# Linear_regulators.net
KiCad netlist of a schematic drawn in Altium Designer
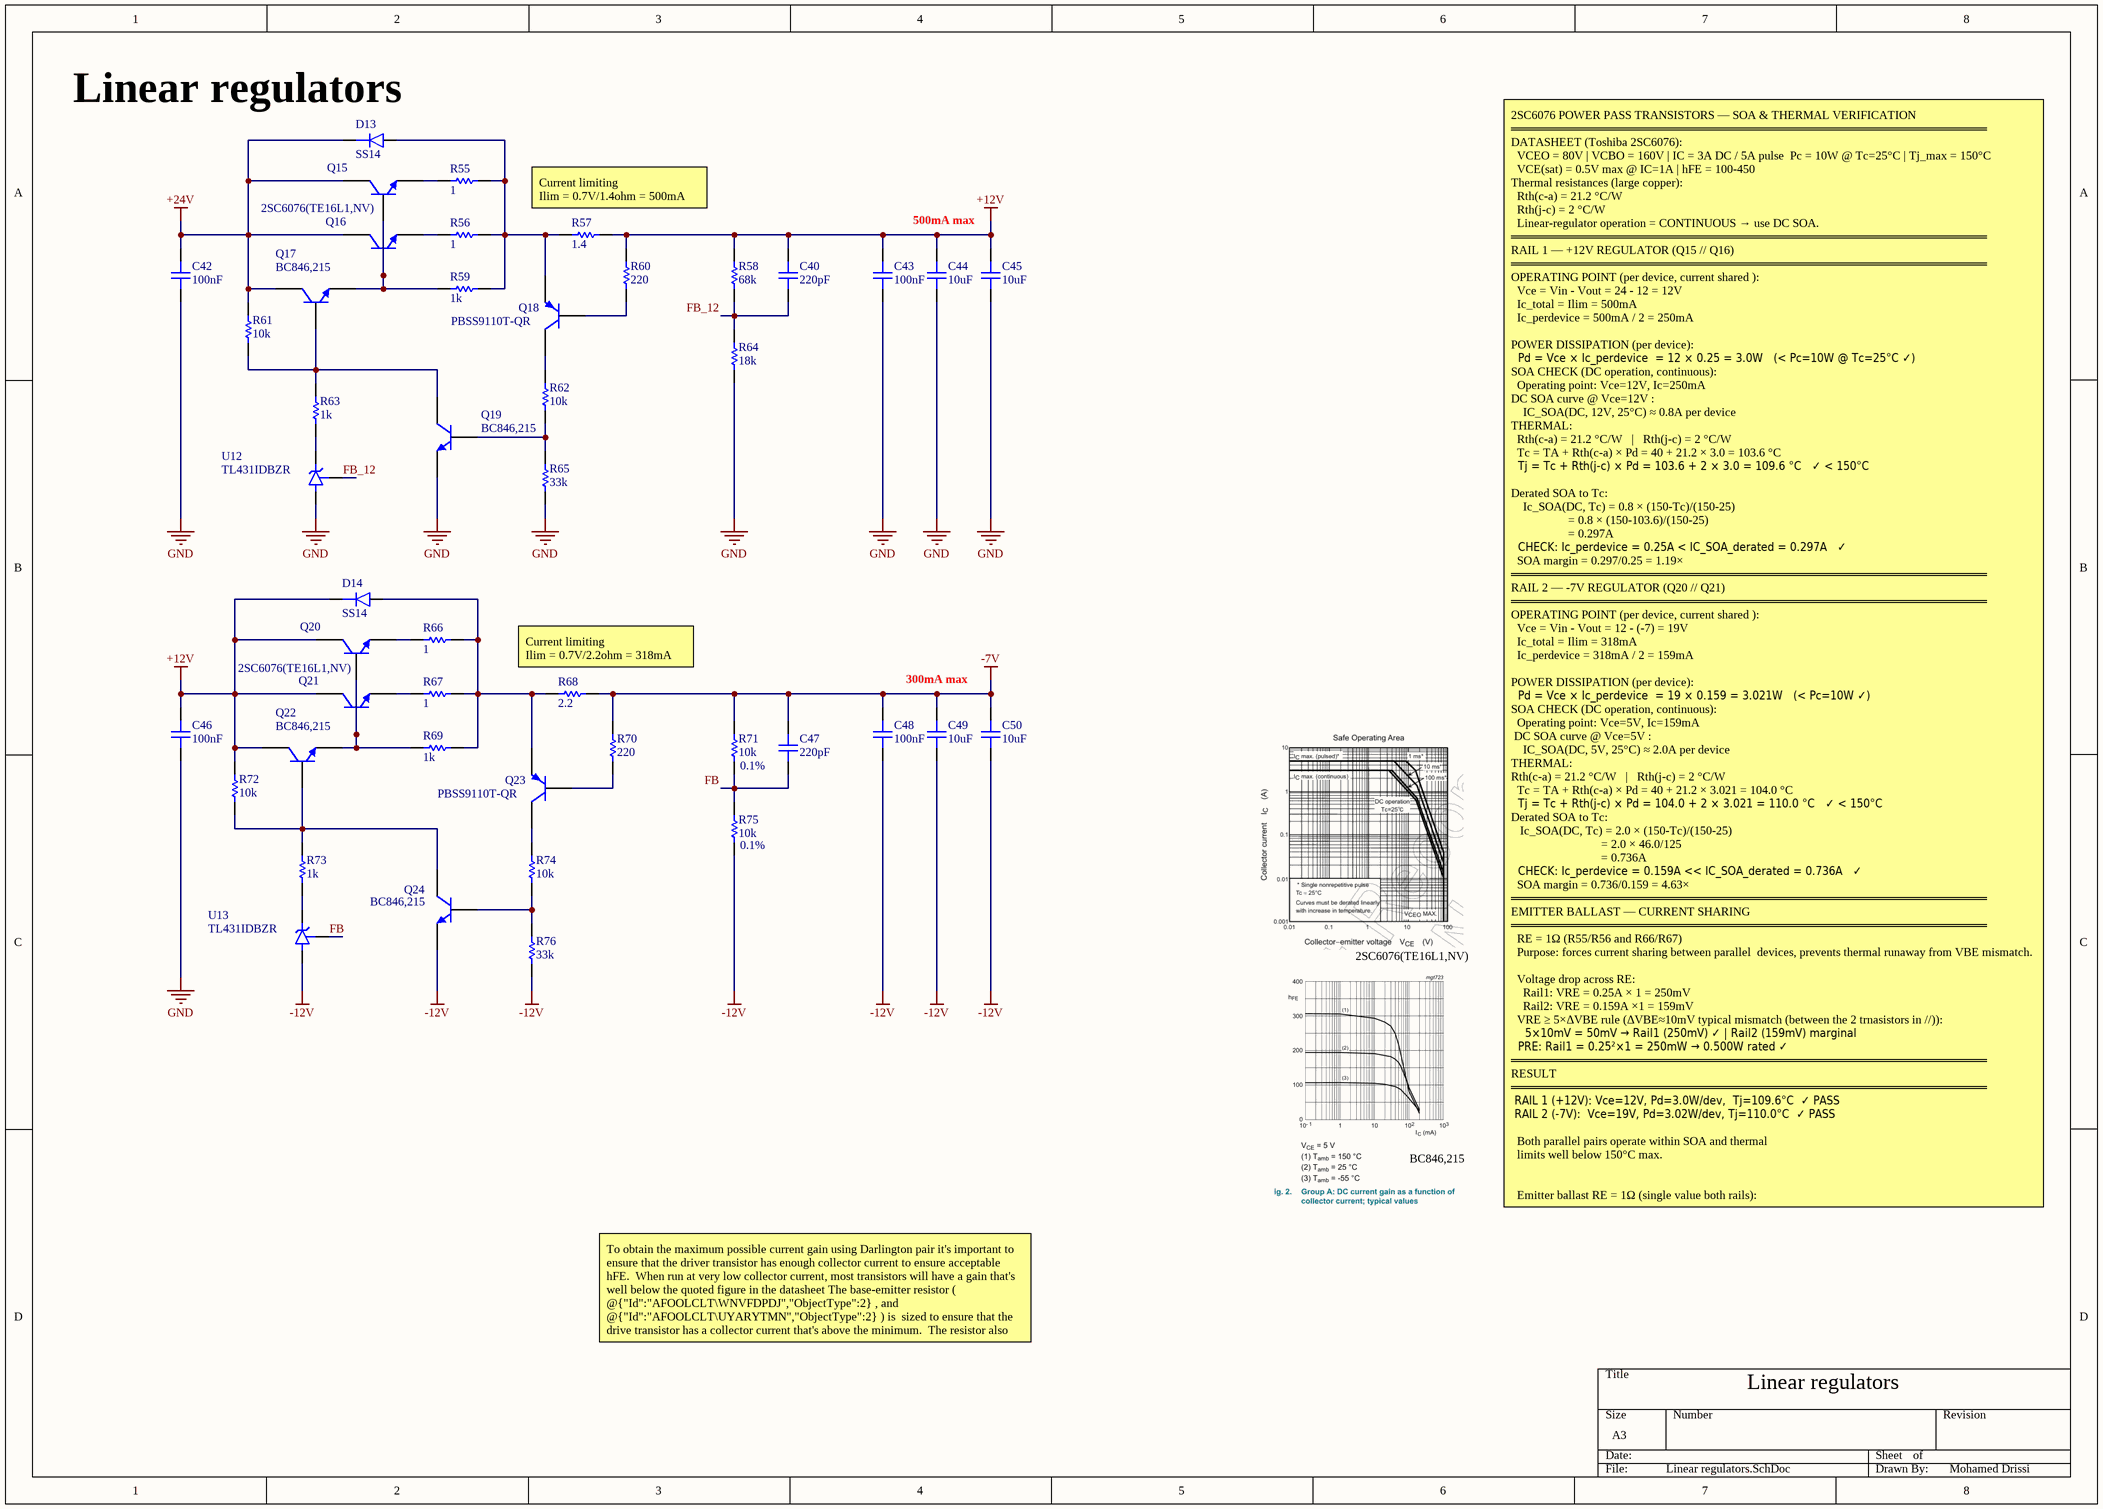
[diagram p0: Linear regulators.SchDoc]

(export (version "E")
  (design (tool "Eeschema 10.0.6"))
  (components
    (comp (ref "C40")
      (value "CC0603JRNPO7BN221")
      (footprint "cap_0603")
      (description "16V 220pF C0G ±5% 0603 Multilayer Ceramic Capacitors MLCC - SMD/SMT ROHS")
      (fields
        (field (name "MANUFACTURER") "Yageo Group")
        (field (name "TOLERANCE") "5%")
        (field (name "CAPACITANCE") "220pF")
      )
      (libsource (lib "Inverting buck boost") (part "Yageo CC0603JRNPO7BN221"))
    )
    (comp (ref "C42")
      (value "GMC10X7R104K100NT")
      (footprint "cap_0603")
      (description "100V 100nF X7R ±10% 0603 Multilayer Ceramic Capacitors MLCC - SMD/SMT ROHS")
      (fields (field (name "MANUFACTURER") "Cal-Chip Electronics") (field (name "CAPACITANCE") "100nF"))
      (libsource (lib "Inverting buck boost") (part "Cal-chip GMC10X7R104K100NT"))
    )
    (comp (ref "C43")
      (value "GMC10X7R104K100NT")
      (footprint "cap_0603")
      (description "100V 100nF X7R ±10% 0603 Multilayer Ceramic Capacitors MLCC - SMD/SMT ROHS")
      (fields (field (name "MANUFACTURER") "Cal-Chip Electronics") (field (name "CAPACITANCE") "100nF"))
      (libsource (lib "Inverting buck boost") (part "Cal-chip GMC10X7R104K100NT"))
    )
    (comp (ref "C44")
      (value "885012209073")
      (footprint "cap_1210")
      (description "Cap, 10Uf, 50V, Mlcc, 1210 Rohs Compliant: Yes ¦Würth Elektronik 885012209073")
      (fields
        (field (name "MANUFACTURER") "Wurth Elektronik")
        (field (name "TOLERANCE") "10%")
        (field (name "CAPACITANCE") "10uF")
      )
      (libsource (lib "Inverting buck boost") (part "Wurth 885012209073"))
    )
    (comp (ref "C45")
      (value "885012209073")
      (footprint "cap_1210")
      (description "Cap, 10Uf, 50V, Mlcc, 1210 Rohs Compliant: Yes ¦Würth Elektronik 885012209073")
      (fields
        (field (name "MANUFACTURER") "Wurth Elektronik")
        (field (name "TOLERANCE") "10%")
        (field (name "CAPACITANCE") "10uF")
      )
      (libsource (lib "Inverting buck boost") (part "Wurth 885012209073"))
    )
    (comp (ref "C46")
      (value "GMC10X7R104K100NT")
      (footprint "cap_0603")
      (description "100V 100nF X7R ±10% 0603 Multilayer Ceramic Capacitors MLCC - SMD/SMT ROHS")
      (fields (field (name "MANUFACTURER") "Cal-Chip Electronics") (field (name "CAPACITANCE") "100nF"))
      (libsource (lib "Inverting buck boost") (part "Cal-chip GMC10X7R104K100NT"))
    )
    (comp (ref "C47")
      (value "CC0603JRNPO7BN221")
      (footprint "cap_0603")
      (description "16V 220pF C0G ±5% 0603 Multilayer Ceramic Capacitors MLCC - SMD/SMT ROHS")
      (fields
        (field (name "MANUFACTURER") "Yageo Group")
        (field (name "TOLERANCE") "5%")
        (field (name "CAPACITANCE") "220pF")
      )
      (libsource (lib "Inverting buck boost") (part "Yageo CC0603JRNPO7BN221"))
    )
    (comp (ref "C48")
      (value "GMC10X7R104K100NT")
      (footprint "cap_0603")
      (description "100V 100nF X7R ±10% 0603 Multilayer Ceramic Capacitors MLCC - SMD/SMT ROHS")
      (fields (field (name "MANUFACTURER") "Cal-Chip Electronics") (field (name "CAPACITANCE") "100nF"))
      (libsource (lib "Inverting buck boost") (part "Cal-chip GMC10X7R104K100NT"))
    )
    (comp (ref "C49")
      (value "885012209073")
      (footprint "cap_1210")
      (description "Cap, 10Uf, 50V, Mlcc, 1210 Rohs Compliant: Yes ¦Würth Elektronik 885012209073")
      (fields
        (field (name "MANUFACTURER") "Wurth Elektronik")
        (field (name "TOLERANCE") "10%")
        (field (name "CAPACITANCE") "10uF")
      )
      (libsource (lib "Inverting buck boost") (part "Wurth 885012209073"))
    )
    (comp (ref "C50")
      (value "885012209073")
      (footprint "cap_1210")
      (description "Cap, 10Uf, 50V, Mlcc, 1210 Rohs Compliant: Yes ¦Würth Elektronik 885012209073")
      (fields
        (field (name "MANUFACTURER") "Wurth Elektronik")
        (field (name "TOLERANCE") "10%")
        (field (name "CAPACITANCE") "10uF")
      )
      (libsource (lib "Inverting buck boost") (part "Wurth 885012209073"))
    )
    (comp (ref "D13")
      (value "SS14")
      (footprint "DO-214AC")
      (description "SS14 Series 500 mV 1 A 40 V Max Reverse Voltage Schottky Rectifier - DO-214AC")
      (fields (field (name "MANUFACTURER") "onsemi") (field (name "VOLTAGE") "30V"))
      (libsource (lib "Inverting buck boost") (part "Onsemi SS14"))
    )
    (comp (ref "D14")
      (value "SS14")
      (footprint "DO-214AC")
      (description "SS14 Series 500 mV 1 A 40 V Max Reverse Voltage Schottky Rectifier - DO-214AC")
      (fields (field (name "MANUFACTURER") "onsemi") (field (name "VOLTAGE") "30V"))
      (libsource (lib "Inverting buck boost") (part "Onsemi SS14"))
    )
    (comp (ref "Q15")
      (value "2SC6076(TE16L1,NV)")
      (footprint "TO-252  (DPAK)")
      (description "Power Bipolar Transistor, 3A I(C), 80V V(BR)CEO, 1-Element, NPN, Silicon, Plastic/Epoxy, 2 Pin")
      (fields (field (name "MANUFACTURER") "Toshiba"))
      (libsource (lib "Inverting buck boost") (part "Toshihba 2SC6076(TE16L1,NV)"))
    )
    (comp (ref "Q16")
      (value "2SC6076(TE16L1,NV)")
      (footprint "TO-252  (DPAK)")
      (description "Power Bipolar Transistor, 3A I(C), 80V V(BR)CEO, 1-Element, NPN, Silicon, Plastic/Epoxy, 2 Pin")
      (fields (field (name "MANUFACTURER") "Toshiba"))
      (libsource (lib "Inverting buck boost") (part "Toshihba 2SC6076(TE16L1,NV)"))
    )
    (comp (ref "Q17")
      (value "BC846,215")
      (footprint "sot23")
      (description "BC846 Series 65 V 100 mA SMT NPN General Purpose Transistor - SOT-23")
      (fields (field (name "MANUFACTURER") "Nexperia"))
      (libsource (lib "Inverting buck boost") (part "NXP BC846,215"))
    )
    (comp (ref "Q18")
      (value "PBSS9110T-QR")
      (footprint "SOT23")
      (description "Bipolar Transistors - BJT 100 V, 1 A PNP low VCEsat transistor")
      (fields (field (name "MANUFACTURER") "Nexperia"))
      (libsource (lib "Inverting buck boost") (part "NXP PBSS9110T-QR"))
    )
    (comp (ref "Q19")
      (value "BC846,215")
      (footprint "sot23")
      (description "BC846 Series 65 V 100 mA SMT NPN General Purpose Transistor - SOT-23")
      (fields (field (name "MANUFACTURER") "Nexperia"))
      (libsource (lib "Inverting buck boost") (part "NXP BC846,215"))
    )
    (comp (ref "Q20")
      (value "2SC6076(TE16L1,NV)")
      (footprint "TO-252  (DPAK)")
      (description "Power Bipolar Transistor, 3A I(C), 80V V(BR)CEO, 1-Element, NPN, Silicon, Plastic/Epoxy, 2 Pin")
      (fields (field (name "MANUFACTURER") "Toshiba"))
      (libsource (lib "Inverting buck boost") (part "Toshihba 2SC6076(TE16L1,NV)"))
    )
    (comp (ref "Q21")
      (value "2SC6076(TE16L1,NV)")
      (footprint "TO-252  (DPAK)")
      (description "Power Bipolar Transistor, 3A I(C), 80V V(BR)CEO, 1-Element, NPN, Silicon, Plastic/Epoxy, 2 Pin")
      (fields (field (name "MANUFACTURER") "Toshiba"))
      (libsource (lib "Inverting buck boost") (part "Toshihba 2SC6076(TE16L1,NV)"))
    )
    (comp (ref "Q22")
      (value "BC846,215")
      (footprint "sot23")
      (description "BC846 Series 65 V 100 mA SMT NPN General Purpose Transistor - SOT-23")
      (fields (field (name "MANUFACTURER") "Nexperia"))
      (libsource (lib "Inverting buck boost") (part "NXP BC846,215"))
    )
    (comp (ref "Q23")
      (value "PBSS9110T-QR")
      (footprint "SOT23")
      (description "Bipolar Transistors - BJT 100 V, 1 A PNP low VCEsat transistor")
      (fields (field (name "MANUFACTURER") "Nexperia"))
      (libsource (lib "Inverting buck boost") (part "NXP PBSS9110T-QR"))
    )
    (comp (ref "Q24")
      (value "BC846,215")
      (footprint "sot23")
      (description "BC846 Series 65 V 100 mA SMT NPN General Purpose Transistor - SOT-23")
      (fields (field (name "MANUFACTURER") "Nexperia"))
      (libsource (lib "Inverting buck boost") (part "NXP BC846,215"))
    )
    (comp (ref "R55")
      (value "RCS06031R00JNEA")
      (footprint "res_0603")
      (description "SMD Chip Resistor, 1 Ohm, ± 5%, 500 mW, 0603 [1608 Metric], Thick Film, Anti-Surge")
      (fields
        (field (name "MANUFACTURER") "Vishay")
        (field (name "TOLERANCE") "5%")
        (field (name "RESISTANCE") "1")
      )
      (libsource (lib "Inverting buck boost") (part "Vishay RCS06031R00JNEA"))
    )
    (comp (ref "R56")
      (value "RCS06031R00JNEA")
      (footprint "res_0603")
      (description "SMD Chip Resistor, 1 Ohm, ± 5%, 500 mW, 0603 [1608 Metric], Thick Film, Anti-Surge")
      (fields
        (field (name "MANUFACTURER") "Vishay")
        (field (name "TOLERANCE") "5%")
        (field (name "RESISTANCE") "1")
      )
      (libsource (lib "Inverting buck boost") (part "Vishay RCS06031R00JNEA"))
    )
    (comp (ref "R57")
      (value "CRCW12061R40FKEAHP")
      (footprint "res_1206")
      (description "Res Thick Film 1206 1.4 Ohm 1% 0.75W(3/4W) ±100ppm/C Pad SMD Automotive T/R")
      (fields
        (field (name "MANUFACTURER") "Vishay")
        (field (name "TOLERANCE") "1%")
        (field (name "RESISTANCE") "1.4")
      )
      (libsource (lib "Inverting buck boost") (part "Vishay CRCW12061R40FKEAHP"))
    )
    (comp (ref "R58")
      (value "CRGCQ0603J68K")
      (footprint "res_0603")
      (description "Res Thick Film 0603 68K Ohm 5% 0.1W(1/10W) ±100ppm/C Pad SMD Automotive T/R")
      (fields
        (field (name "MANUFACTURER") "TE Connectivity")
        (field (name "TOLERANCE") "5%")
        (field (name "RESISTANCE") "68k")
      )
      (libsource (lib "Inverting buck boost") (part "TE CRGCQ0603J68K"))
    )
    (comp (ref "R59")
      (value "RC0603FR-071KL")
      (footprint "res_0603")
      (description "Res Thick Film 0603 1K Ohm 1% 0.1W(1/10W) ±100ppm/°C Pad SMD T/R / RES SMD 1K OHM 1% 1/10W 0603")
      (fields
        (field (name "MANUFACTURER") "Yageo Group")
        (field (name "TOLERANCE") "1%")
        (field (name "RESISTANCE") "1k")
      )
      (libsource (lib "Inverting buck boost") (part "Yageo RC0603FR-071KL"))
    )
    (comp (ref "R60")
      (value "CRGCQ0603J220R")
      (footprint "res_0603")
      (description "Res Thick Film 0603 220 Ohm 5% 0.1W(1/10W) ±100ppm/C Pad SMD Automotive T/R")
      (fields
        (field (name "MANUFACTURER") "TE Connectivity")
        (field (name "TOLERANCE") "5%")
        (field (name "RESISTANCE") "220")
      )
      (libsource (lib "Inverting buck boost") (part "TE CRGCQ0603J220R"))
    )
    (comp (ref "R61")
      (value "ERA-3AEB103V")
      (footprint "res_0603")
      (description "Res Thin Film 0603 10K Ohm 0.1% 1/10W ±25ppm/°C Molded SMD SMD Punched Carrier T/R")
      (fields
        (field (name "MANUFACTURER") "Panasonic")
        (field (name "TOLERANCE") "0.1%")
        (field (name "RESISTANCE") "10k")
      )
      (libsource (lib "Inverting buck boost") (part "Panasonic ERA-3AEB103V"))
    )
    (comp (ref "R62")
      (value "ERA-3AEB103V")
      (footprint "res_0603")
      (description "Res Thin Film 0603 10K Ohm 0.1% 1/10W ±25ppm/°C Molded SMD SMD Punched Carrier T/R")
      (fields
        (field (name "MANUFACTURER") "Panasonic")
        (field (name "TOLERANCE") "0.1%")
        (field (name "RESISTANCE") "10k")
      )
      (libsource (lib "Inverting buck boost") (part "Panasonic ERA-3AEB103V"))
    )
    (comp (ref "R63")
      (value "RC0603FR-071KL")
      (footprint "res_0603")
      (description "Res Thick Film 0603 1K Ohm 1% 0.1W(1/10W) ±100ppm/°C Pad SMD T/R / RES SMD 1K OHM 1% 1/10W 0603")
      (fields
        (field (name "MANUFACTURER") "Yageo Group")
        (field (name "TOLERANCE") "1%")
        (field (name "RESISTANCE") "1k")
      )
      (libsource (lib "Inverting buck boost") (part "Yageo RC0603FR-071KL"))
    )
    (comp (ref "R64")
      (value "CRCW060318K0FKEAC")
      (footprint "res_0603")
      (description "CRCW Thick Film Commodity Chip Resistor 0603 Size 18K Ohm 1% 0.1 W 100 ppm/K 2-Pin SMD Paper T/R")
      (fields
        (field (name "MANUFACTURER") "Vishay")
        (field (name "TOLERANCE") "1%")
        (field (name "RESISTANCE") "18k")
      )
      (libsource (lib "Inverting buck boost") (part "Vishay CRCW060318K0FKEAC"))
    )
    (comp (ref "R65")
      (value "RC0603JR-0733KL")
      (footprint "res_0603")
      (description "100mW Thick Film Resistors 75V ±100ppm/℃ ±5% 33kΩ 0603 Chip Resistor - Surface Mount ROHS")
      (fields
        (field (name "MANUFACTURER") "Yageo Group")
        (field (name "TOLERANCE") "5%")
        (field (name "RESISTANCE") "33k")
      )
      (libsource (lib "Inverting buck boost") (part "Yageo RC0603JR-0733KL"))
    )
    (comp (ref "R66")
      (value "RCS06031R00JNEA")
      (footprint "res_0603")
      (description "SMD Chip Resistor, 1 Ohm, ± 5%, 500 mW, 0603 [1608 Metric], Thick Film, Anti-Surge")
      (fields
        (field (name "MANUFACTURER") "Vishay")
        (field (name "TOLERANCE") "5%")
        (field (name "RESISTANCE") "1")
      )
      (libsource (lib "Inverting buck boost") (part "Vishay RCS06031R00JNEA"))
    )
    (comp (ref "R67")
      (value "RCS06031R00JNEA")
      (footprint "res_0603")
      (description "SMD Chip Resistor, 1 Ohm, ± 5%, 500 mW, 0603 [1608 Metric], Thick Film, Anti-Surge")
      (fields
        (field (name "MANUFACTURER") "Vishay")
        (field (name "TOLERANCE") "5%")
        (field (name "RESISTANCE") "1")
      )
      (libsource (lib "Inverting buck boost") (part "Vishay RCS06031R00JNEA"))
    )
    (comp (ref "R68")
      (value "CRM1206-JW-2R2ELF")
      (footprint "res_1206")
      (description "Res Thick Film 1206 2.2 Ohm 5% 0.5W(1/2W) ±200ppm/C Pad SMD T/R")
      (fields
        (field (name "MANUFACTURER") "Bourns")
        (field (name "TOLERANCE") "5%")
        (field (name "RESISTANCE") "2.2")
      )
      (libsource (lib "Inverting buck boost") (part "Bourns CRM1206-JW-2R2ELF"))
    )
    (comp (ref "R69")
      (value "RC0603FR-071KL")
      (footprint "res_0603")
      (description "Res Thick Film 0603 1K Ohm 1% 0.1W(1/10W) ±100ppm/°C Pad SMD T/R / RES SMD 1K OHM 1% 1/10W 0603")
      (fields
        (field (name "MANUFACTURER") "Yageo Group")
        (field (name "TOLERANCE") "1%")
        (field (name "RESISTANCE") "1k")
      )
      (libsource (lib "Inverting buck boost") (part "Yageo RC0603FR-071KL"))
    )
    (comp (ref "R70")
      (value "CRGCQ0603J220R")
      (footprint "res_0603")
      (description "Res Thick Film 0603 220 Ohm 5% 0.1W(1/10W) ±100ppm/C Pad SMD Automotive T/R")
      (fields
        (field (name "MANUFACTURER") "TE Connectivity")
        (field (name "TOLERANCE") "5%")
        (field (name "RESISTANCE") "220")
      )
      (libsource (lib "Inverting buck boost") (part "TE CRGCQ0603J220R"))
    )
    (comp (ref "R71")
      (value "ERA-3AEB103V")
      (footprint "res_0603")
      (description "Res Thin Film 0603 10K Ohm 0.1% 1/10W ±25ppm/°C Molded SMD SMD Punched Carrier T/R")
      (fields
        (field (name "MANUFACTURER") "Panasonic")
        (field (name "TOLERANCE") "0.1%")
        (field (name "RESISTANCE") "10k")
      )
      (libsource (lib "Inverting buck boost") (part "Panasonic ERA-3AEB103V"))
    )
    (comp (ref "R72")
      (value "ERA-3AEB103V")
      (footprint "res_0603")
      (description "Res Thin Film 0603 10K Ohm 0.1% 1/10W ±25ppm/°C Molded SMD SMD Punched Carrier T/R")
      (fields
        (field (name "MANUFACTURER") "Panasonic")
        (field (name "TOLERANCE") "0.1%")
        (field (name "RESISTANCE") "10k")
      )
      (libsource (lib "Inverting buck boost") (part "Panasonic ERA-3AEB103V"))
    )
    (comp (ref "R73")
      (value "RC0603FR-071KL")
      (footprint "res_0603")
      (description "Res Thick Film 0603 1K Ohm 1% 0.1W(1/10W) ±100ppm/°C Pad SMD T/R / RES SMD 1K OHM 1% 1/10W 0603")
      (fields
        (field (name "MANUFACTURER") "Yageo Group")
        (field (name "TOLERANCE") "1%")
        (field (name "RESISTANCE") "1k")
      )
      (libsource (lib "Inverting buck boost") (part "Yageo RC0603FR-071KL"))
    )
    (comp (ref "R74")
      (value "ERA-3AEB103V")
      (footprint "res_0603")
      (description "Res Thin Film 0603 10K Ohm 0.1% 1/10W ±25ppm/°C Molded SMD SMD Punched Carrier T/R")
      (fields
        (field (name "MANUFACTURER") "Panasonic")
        (field (name "TOLERANCE") "0.1%")
        (field (name "RESISTANCE") "10k")
      )
      (libsource (lib "Inverting buck boost") (part "Panasonic ERA-3AEB103V"))
    )
    (comp (ref "R75")
      (value "ERA-3AEB103V")
      (footprint "res_0603")
      (description "Res Thin Film 0603 10K Ohm 0.1% 1/10W ±25ppm/°C Molded SMD SMD Punched Carrier T/R")
      (fields
        (field (name "MANUFACTURER") "Panasonic")
        (field (name "TOLERANCE") "0.1%")
        (field (name "RESISTANCE") "10k")
      )
      (libsource (lib "Inverting buck boost") (part "Panasonic ERA-3AEB103V"))
    )
    (comp (ref "R76")
      (value "RC0603JR-0733KL")
      (footprint "res_0603")
      (description "100mW Thick Film Resistors 75V ±100ppm/℃ ±5% 33kΩ 0603 Chip Resistor - Surface Mount ROHS")
      (fields
        (field (name "MANUFACTURER") "Yageo Group")
        (field (name "TOLERANCE") "5%")
        (field (name "RESISTANCE") "33k")
      )
      (libsource (lib "Inverting buck boost") (part "Yageo RC0603JR-0733KL"))
    )
    (comp (ref "U12")
      (value "TL431IDBZR")
      (footprint "SOT-23-3")
      (description "V-Ref Adjustable 2.495V to 36V 100mA Automotive 3-Pin SOT-23 T/R")
      (fields (field (name "MANUFACTURER") "Texas Instruments") (field (name "TOLERANCE") "2%"))
      (libsource (lib "Inverting buck boost") (part "TI TL431IDBZR"))
    )
    (comp (ref "U13")
      (value "TL431IDBZR")
      (footprint "SOT-23-3")
      (description "V-Ref Adjustable 2.495V to 36V 100mA Automotive 3-Pin SOT-23 T/R")
      (fields (field (name "MANUFACTURER") "Texas Instruments") (field (name "TOLERANCE") "2%"))
      (libsource (lib "Inverting buck boost") (part "TI TL431IDBZR"))
    )
  )
  (nets
    (net (code "1") (name "+12V") (class "Default")
      (node (ref "C40") (pin "2") (pinfunction "2_2") (pintype "passive"))
      (node (ref "C43") (pin "2") (pinfunction "2_2") (pintype "passive"))
      (node (ref "C44") (pin "2") (pinfunction "2_2") (pintype "passive"))
      (node (ref "C45") (pin "2") (pinfunction "2_2") (pintype "passive"))
      (node (ref "C46") (pin "2") (pinfunction "2_2") (pintype "passive"))
      (node (ref "D14") (pin "C") (pinfunction "C_C") (pintype "passive"))
      (node (ref "Q20") (pin "2") (pinfunction "C_2") (pintype "passive"))
      (node (ref "Q21") (pin "2") (pinfunction "C_2") (pintype "passive"))
      (node (ref "Q22") (pin "3") (pinfunction "C_3") (pintype "passive"))
      (node (ref "R57") (pin "2") (pinfunction "2_2") (pintype "passive"))
      (node (ref "R58") (pin "2") (pinfunction "2_2") (pintype "passive"))
      (node (ref "R60") (pin "2") (pinfunction "2_2") (pintype "passive"))
      (node (ref "R72") (pin "2") (pinfunction "2_2") (pintype "passive"))
    )
    (net (code "2") (name "+24V") (class "Default")
      (node (ref "C42") (pin "2") (pinfunction "2_2") (pintype "passive"))
      (node (ref "D13") (pin "C") (pinfunction "C_C") (pintype "passive"))
      (node (ref "Q15") (pin "2") (pinfunction "C_2") (pintype "passive"))
      (node (ref "Q16") (pin "2") (pinfunction "C_2") (pintype "passive"))
      (node (ref "Q17") (pin "3") (pinfunction "C_3") (pintype "passive"))
      (node (ref "R61") (pin "2") (pinfunction "2_2") (pintype "passive"))
    )
    (net (code "3") (name "-7V") (class "Default")
      (node (ref "C47") (pin "2") (pinfunction "2_2") (pintype "passive"))
      (node (ref "C48") (pin "2") (pinfunction "2_2") (pintype "passive"))
      (node (ref "C49") (pin "2") (pinfunction "2_2") (pintype "passive"))
      (node (ref "C50") (pin "2") (pinfunction "2_2") (pintype "passive"))
      (node (ref "R68") (pin "1") (pinfunction "1_1") (pintype "passive"))
      (node (ref "R70") (pin "2") (pinfunction "2_2") (pintype "passive"))
      (node (ref "R71") (pin "2") (pinfunction "2_2") (pintype "passive"))
    )
    (net (code "4") (name "-12V") (class "Default")
      (node (ref "C48") (pin "1") (pinfunction "1_1") (pintype "passive"))
      (node (ref "C49") (pin "1") (pinfunction "1_1") (pintype "passive"))
      (node (ref "C50") (pin "1") (pinfunction "1_1") (pintype "passive"))
      (node (ref "Q24") (pin "2") (pinfunction "E_2") (pintype "passive"))
      (node (ref "R75") (pin "1") (pinfunction "1_1") (pintype "passive"))
      (node (ref "R76") (pin "1") (pinfunction "1_1") (pintype "passive"))
      (node (ref "U13") (pin "3") (pinfunction "A_3") (pintype "passive"))
    )
    (net (code "5") (name "/FB") (class "Default")
      (node (ref "C47") (pin "1") (pinfunction "1_1") (pintype "passive"))
      (node (ref "R71") (pin "1") (pinfunction "1_1") (pintype "passive"))
      (node (ref "R75") (pin "2") (pinfunction "2_2") (pintype "passive"))
      (node (ref "U13") (pin "2") (pinfunction "REF_2") (pintype "passive"))
    )
    (net (code "6") (name "/FB_12") (class "Default")
      (node (ref "C40") (pin "1") (pinfunction "1_1") (pintype "passive"))
      (node (ref "R58") (pin "1") (pinfunction "1_1") (pintype "passive"))
      (node (ref "R64") (pin "2") (pinfunction "2_2") (pintype "passive"))
      (node (ref "U12") (pin "2") (pinfunction "REF_2") (pintype "passive"))
    )
    (net (code "7") (name "GND") (class "Default")
      (node (ref "C42") (pin "1") (pinfunction "1_1") (pintype "passive"))
      (node (ref "C43") (pin "1") (pinfunction "1_1") (pintype "passive"))
      (node (ref "C44") (pin "1") (pinfunction "1_1") (pintype "passive"))
      (node (ref "C45") (pin "1") (pinfunction "1_1") (pintype "passive"))
      (node (ref "C46") (pin "1") (pinfunction "1_1") (pintype "passive"))
      (node (ref "Q19") (pin "2") (pinfunction "E_2") (pintype "passive"))
      (node (ref "R64") (pin "1") (pinfunction "1_1") (pintype "passive"))
      (node (ref "R65") (pin "1") (pinfunction "1_1") (pintype "passive"))
      (node (ref "U12") (pin "3") (pinfunction "A_3") (pintype "passive"))
    )
    (net (code "8") (name "Net-(Q15-B)") (class "Default")
      (node (ref "Q15") (pin "1") (pinfunction "B_1") (pintype "passive"))
      (node (ref "Q16") (pin "1") (pinfunction "B_1") (pintype "passive"))
      (node (ref "Q17") (pin "2") (pinfunction "E_2") (pintype "passive"))
      (node (ref "R59") (pin "1") (pinfunction "1_1") (pintype "passive"))
    )
    (net (code "9") (name "Net-(Q15-E)") (class "Default")
      (node (ref "Q15") (pin "3") (pinfunction "E_3") (pintype "passive"))
      (node (ref "R55") (pin "1") (pinfunction "1_1") (pintype "passive"))
    )
    (net (code "10") (name "Net-(Q16-E)") (class "Default")
      (node (ref "Q16") (pin "3") (pinfunction "E_3") (pintype "passive"))
      (node (ref "R56") (pin "1") (pinfunction "1_1") (pintype "passive"))
    )
    (net (code "11") (name "Net-(Q17-B)") (class "Default")
      (node (ref "Q17") (pin "1") (pinfunction "B_1") (pintype "passive"))
      (node (ref "Q19") (pin "3") (pinfunction "C_3") (pintype "passive"))
      (node (ref "R61") (pin "1") (pinfunction "1_1") (pintype "passive"))
      (node (ref "R63") (pin "2") (pinfunction "2_2") (pintype "passive"))
    )
    (net (code "12") (name "Net-(Q18-B)") (class "Default")
      (node (ref "Q18") (pin "1") (pinfunction "B_1") (pintype "passive"))
      (node (ref "R60") (pin "1") (pinfunction "1_1") (pintype "passive"))
    )
    (net (code "13") (name "Net-(Q18-C)") (class "Default")
      (node (ref "Q18") (pin "3") (pinfunction "C_3") (pintype "passive"))
      (node (ref "R62") (pin "2") (pinfunction "2_2") (pintype "passive"))
    )
    (net (code "14") (name "Net-(Q18-E)") (class "Default")
      (node (ref "D13") (pin "A") (pinfunction "A_A") (pintype "passive"))
      (node (ref "Q18") (pin "2") (pinfunction "E_2") (pintype "passive"))
      (node (ref "R55") (pin "2") (pinfunction "2_2") (pintype "passive"))
      (node (ref "R56") (pin "2") (pinfunction "2_2") (pintype "passive"))
      (node (ref "R57") (pin "1") (pinfunction "1_1") (pintype "passive"))
      (node (ref "R59") (pin "2") (pinfunction "2_2") (pintype "passive"))
    )
    (net (code "15") (name "Net-(Q19-B)") (class "Default")
      (node (ref "Q19") (pin "1") (pinfunction "B_1") (pintype "passive"))
      (node (ref "R62") (pin "1") (pinfunction "1_1") (pintype "passive"))
      (node (ref "R65") (pin "2") (pinfunction "2_2") (pintype "passive"))
    )
    (net (code "16") (name "Net-(Q20-B)") (class "Default")
      (node (ref "Q20") (pin "1") (pinfunction "B_1") (pintype "passive"))
      (node (ref "Q21") (pin "1") (pinfunction "B_1") (pintype "passive"))
      (node (ref "Q22") (pin "2") (pinfunction "E_2") (pintype "passive"))
      (node (ref "R69") (pin "1") (pinfunction "1_1") (pintype "passive"))
    )
    (net (code "17") (name "Net-(Q20-E)") (class "Default")
      (node (ref "Q20") (pin "3") (pinfunction "E_3") (pintype "passive"))
      (node (ref "R66") (pin "1") (pinfunction "1_1") (pintype "passive"))
    )
    (net (code "18") (name "Net-(Q21-E)") (class "Default")
      (node (ref "Q21") (pin "3") (pinfunction "E_3") (pintype "passive"))
      (node (ref "R67") (pin "1") (pinfunction "1_1") (pintype "passive"))
    )
    (net (code "19") (name "Net-(Q22-B)") (class "Default")
      (node (ref "Q22") (pin "1") (pinfunction "B_1") (pintype "passive"))
      (node (ref "Q24") (pin "3") (pinfunction "C_3") (pintype "passive"))
      (node (ref "R72") (pin "1") (pinfunction "1_1") (pintype "passive"))
      (node (ref "R73") (pin "2") (pinfunction "2_2") (pintype "passive"))
    )
    (net (code "20") (name "Net-(Q23-B)") (class "Default")
      (node (ref "Q23") (pin "1") (pinfunction "B_1") (pintype "passive"))
      (node (ref "R70") (pin "1") (pinfunction "1_1") (pintype "passive"))
    )
    (net (code "21") (name "Net-(Q23-C)") (class "Default")
      (node (ref "Q23") (pin "3") (pinfunction "C_3") (pintype "passive"))
      (node (ref "R74") (pin "2") (pinfunction "2_2") (pintype "passive"))
    )
    (net (code "22") (name "Net-(Q23-E)") (class "Default")
      (node (ref "D14") (pin "A") (pinfunction "A_A") (pintype "passive"))
      (node (ref "Q23") (pin "2") (pinfunction "E_2") (pintype "passive"))
      (node (ref "R66") (pin "2") (pinfunction "2_2") (pintype "passive"))
      (node (ref "R67") (pin "2") (pinfunction "2_2") (pintype "passive"))
      (node (ref "R68") (pin "2") (pinfunction "2_2") (pintype "passive"))
      (node (ref "R69") (pin "2") (pinfunction "2_2") (pintype "passive"))
    )
    (net (code "23") (name "Net-(Q24-B)") (class "Default")
      (node (ref "Q24") (pin "1") (pinfunction "B_1") (pintype "passive"))
      (node (ref "R74") (pin "1") (pinfunction "1_1") (pintype "passive"))
      (node (ref "R76") (pin "2") (pinfunction "2_2") (pintype "passive"))
    )
    (net (code "24") (name "Net-(U12-K)") (class "Default")
      (node (ref "R63") (pin "1") (pinfunction "1_1") (pintype "passive"))
      (node (ref "U12") (pin "1") (pinfunction "K_1") (pintype "passive"))
    )
    (net (code "25") (name "Net-(U13-K)") (class "Default")
      (node (ref "R73") (pin "1") (pinfunction "1_1") (pintype "passive"))
      (node (ref "U13") (pin "1") (pinfunction "K_1") (pintype "passive"))
    )
  )
)
